# abxy.net
KiCad netlist of a schematic drawn in EAGLE
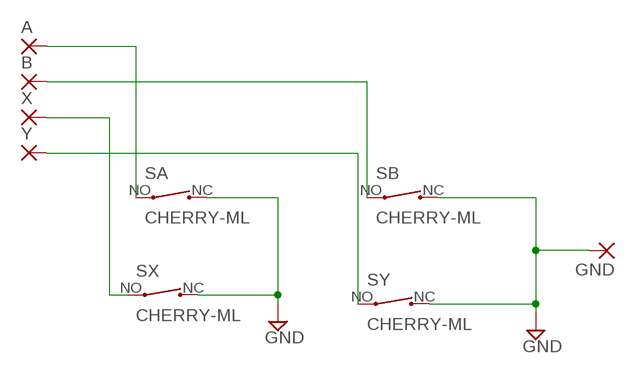
[diagram p0: schematic, sheet 1]

(export (version "E")
  (design (tool "Eeschema 10.0.6"))
  (components
    (comp (ref "A")
      (value "3,81/1,3")
      (footprint "eagle-import:3,81_1,3")
      (libsource (lib "eagle-import") (part "3,81/1,3"))
    )
    (comp (ref "B")
      (value "3,81/1,3")
      (footprint "eagle-import:3,81_1,3")
      (libsource (lib "eagle-import") (part "3,81/1,3"))
    )
    (comp (ref "GND")
      (value "2,15/1,0")
      (footprint "eagle-import:2,15_1,0")
      (libsource (lib "eagle-import") (part "2,15/1,0"))
    )
    (comp (ref "SA")
      (value "CHERRY-ML")
      (footprint "eagle-import:CHERRY-ML")
      (libsource (lib "eagle-import") (part "CHERRY-ML"))
    )
    (comp (ref "SB")
      (value "CHERRY-ML")
      (footprint "eagle-import:CHERRY-ML")
      (libsource (lib "eagle-import") (part "CHERRY-ML"))
    )
    (comp (ref "SX")
      (value "CHERRY-ML")
      (footprint "eagle-import:CHERRY-ML")
      (libsource (lib "eagle-import") (part "CHERRY-ML"))
    )
    (comp (ref "SY")
      (value "CHERRY-ML")
      (footprint "eagle-import:CHERRY-ML")
      (libsource (lib "eagle-import") (part "CHERRY-ML"))
    )
    (comp (ref "X")
      (value "3,81/1,3")
      (footprint "eagle-import:3,81_1,3")
      (libsource (lib "eagle-import") (part "3,81/1,3"))
    )
    (comp (ref "Y")
      (value "3,81/1,3")
      (footprint "eagle-import:3,81_1,3")
      (libsource (lib "eagle-import") (part "3,81/1,3"))
    )
  )
  (nets
    (net (code "1") (name "GND") (class "Default")
      (node (ref "GND") (pin "1") (pinfunction "P_1") (pintype "passive"))
      (node (ref "SA") (pin "NC") (pinfunction "2_NC") (pintype "passive"))
      (node (ref "SB") (pin "NC") (pinfunction "2_NC") (pintype "passive"))
      (node (ref "SX") (pin "NC") (pinfunction "2_NC") (pintype "passive"))
      (node (ref "SY") (pin "NC") (pinfunction "2_NC") (pintype "passive"))
    )
    (net (code "2") (name "Net-(A-P)") (class "Default")
      (node (ref "A") (pin "1") (pinfunction "P_1") (pintype "passive"))
      (node (ref "SA") (pin "NO") (pinfunction "1_NO") (pintype "passive"))
    )
    (net (code "3") (name "Net-(B-P)") (class "Default")
      (node (ref "B") (pin "1") (pinfunction "P_1") (pintype "passive"))
      (node (ref "SB") (pin "NO") (pinfunction "1_NO") (pintype "passive"))
    )
    (net (code "4") (name "Net-(SX-1)") (class "Default")
      (node (ref "SX") (pin "NO") (pinfunction "1_NO") (pintype "passive"))
      (node (ref "X") (pin "1") (pinfunction "P_1") (pintype "passive"))
    )
    (net (code "5") (name "Net-(SY-1)") (class "Default")
      (node (ref "SY") (pin "NO") (pinfunction "1_NO") (pintype "passive"))
      (node (ref "Y") (pin "1") (pinfunction "P_1") (pintype "passive"))
    )
  )
)
